# adaptor.net
KiCad netlist of a schematic drawn in EAGLE
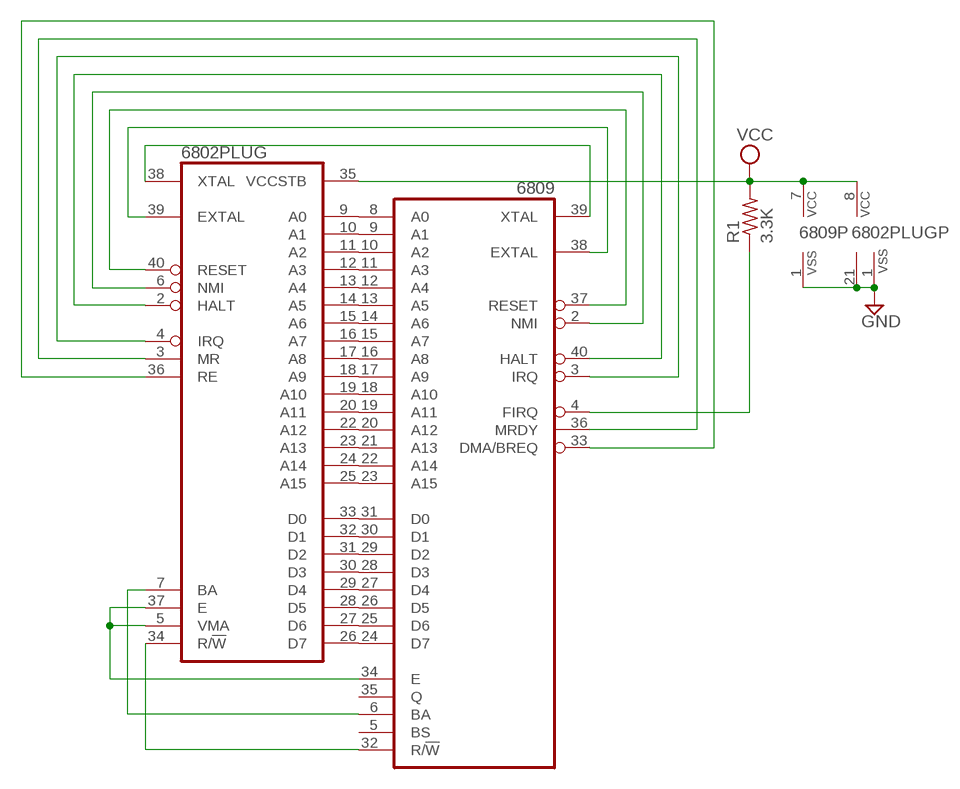
[diagram p0: schematic, sheet 1]

(export (version "E")
  (design (tool "Eeschema 10.0.6"))
  (components
    (comp (ref "6802PLUG")
      (value "6802")
      (footprint "eagle-import:DIL40")
      (libsource (lib "eagle-import") (part "6802"))
    )
    (comp (ref "6809")
      (value "6809")
      (footprint "eagle-import:DIL40")
      (fields (field (name "MF") "NTE ELECTRONICS") (field (name "MPN") "NTE6809"))
      (libsource (lib "eagle-import") (part "6809"))
    )
    (comp (ref "R1")
      (value "3.3K")
      (footprint "eagle-import:0207_10")
      (libsource (lib "eagle-import") (part "R-US_0207/10"))
    )
  )
  (nets
    (net (code "1") (name "GND") (class "Default")
      (node (ref "6802PLUG") (pin "1") (pinfunction "VSS_1") (pintype "power_in"))
      (node (ref "6802PLUG") (pin "21") (pinfunction "VSS_21") (pintype "power_in"))
      (node (ref "6809") (pin "1") (pinfunction "VSS_1") (pintype "power_in"))
    )
    (net (code "2") (name "Net-(6802PLUGA-A0)") (class "Default")
      (node (ref "6802PLUG") (pin "9") (pinfunction "A0_9") (pintype "output"))
      (node (ref "6809") (pin "8") (pinfunction "A0_8") (pintype "tri_state"))
    )
    (net (code "3") (name "Net-(6802PLUGA-A1)") (class "Default")
      (node (ref "6802PLUG") (pin "10") (pinfunction "A1_10") (pintype "output"))
      (node (ref "6809") (pin "9") (pinfunction "A1_9") (pintype "tri_state"))
    )
    (net (code "4") (name "Net-(6802PLUGA-A2)") (class "Default")
      (node (ref "6802PLUG") (pin "11") (pinfunction "A2_11") (pintype "output"))
      (node (ref "6809") (pin "10") (pinfunction "A2_10") (pintype "tri_state"))
    )
    (net (code "5") (name "Net-(6802PLUGA-A3)") (class "Default")
      (node (ref "6802PLUG") (pin "12") (pinfunction "A3_12") (pintype "output"))
      (node (ref "6809") (pin "11") (pinfunction "A3_11") (pintype "tri_state"))
    )
    (net (code "6") (name "Net-(6802PLUGA-A4)") (class "Default")
      (node (ref "6802PLUG") (pin "13") (pinfunction "A4_13") (pintype "output"))
      (node (ref "6809") (pin "12") (pinfunction "A4_12") (pintype "tri_state"))
    )
    (net (code "7") (name "Net-(6802PLUGA-A5)") (class "Default")
      (node (ref "6802PLUG") (pin "14") (pinfunction "A5_14") (pintype "output"))
      (node (ref "6809") (pin "13") (pinfunction "A5_13") (pintype "tri_state"))
    )
    (net (code "8") (name "Net-(6802PLUGA-A6)") (class "Default")
      (node (ref "6802PLUG") (pin "15") (pinfunction "A6_15") (pintype "output"))
      (node (ref "6809") (pin "14") (pinfunction "A6_14") (pintype "tri_state"))
    )
    (net (code "9") (name "Net-(6802PLUGA-A7)") (class "Default")
      (node (ref "6802PLUG") (pin "16") (pinfunction "A7_16") (pintype "output"))
      (node (ref "6809") (pin "15") (pinfunction "A7_15") (pintype "tri_state"))
    )
    (net (code "10") (name "Net-(6802PLUGA-A8)") (class "Default")
      (node (ref "6802PLUG") (pin "17") (pinfunction "A8_17") (pintype "output"))
      (node (ref "6809") (pin "16") (pinfunction "A8_16") (pintype "tri_state"))
    )
    (net (code "11") (name "Net-(6802PLUGA-A9)") (class "Default")
      (node (ref "6802PLUG") (pin "18") (pinfunction "A9_18") (pintype "output"))
      (node (ref "6809") (pin "17") (pinfunction "A9_17") (pintype "tri_state"))
    )
    (net (code "12") (name "Net-(6802PLUGA-A10)") (class "Default")
      (node (ref "6802PLUG") (pin "19") (pinfunction "A10_19") (pintype "output"))
      (node (ref "6809") (pin "18") (pinfunction "A10_18") (pintype "tri_state"))
    )
    (net (code "13") (name "Net-(6802PLUGA-A11)") (class "Default")
      (node (ref "6802PLUG") (pin "20") (pinfunction "A11_20") (pintype "output"))
      (node (ref "6809") (pin "19") (pinfunction "A11_19") (pintype "tri_state"))
    )
    (net (code "14") (name "Net-(6802PLUGA-A12)") (class "Default")
      (node (ref "6802PLUG") (pin "22") (pinfunction "A12_22") (pintype "output"))
      (node (ref "6809") (pin "20") (pinfunction "A12_20") (pintype "tri_state"))
    )
    (net (code "15") (name "Net-(6802PLUGA-A13)") (class "Default")
      (node (ref "6802PLUG") (pin "23") (pinfunction "A13_23") (pintype "output"))
      (node (ref "6809") (pin "21") (pinfunction "A13_21") (pintype "tri_state"))
    )
    (net (code "16") (name "Net-(6802PLUGA-A14)") (class "Default")
      (node (ref "6802PLUG") (pin "24") (pinfunction "A14_24") (pintype "output"))
      (node (ref "6809") (pin "22") (pinfunction "A14_22") (pintype "tri_state"))
    )
    (net (code "17") (name "Net-(6802PLUGA-A15)") (class "Default")
      (node (ref "6802PLUG") (pin "25") (pinfunction "A15_25") (pintype "output"))
      (node (ref "6809") (pin "23") (pinfunction "A15_23") (pintype "tri_state"))
    )
    (net (code "18") (name "Net-(6802PLUGA-BA)") (class "Default")
      (node (ref "6802PLUG") (pin "7") (pinfunction "BA_7") (pintype "output"))
      (node (ref "6809") (pin "6") (pinfunction "BA_6") (pintype "output"))
    )
    (net (code "19") (name "Net-(6802PLUGA-D0)") (class "Default")
      (node (ref "6802PLUG") (pin "33") (pinfunction "D0_33") (pintype "bidirectional"))
      (node (ref "6809") (pin "31") (pinfunction "D0_31") (pintype "bidirectional"))
    )
    (net (code "20") (name "Net-(6802PLUGA-D1)") (class "Default")
      (node (ref "6802PLUG") (pin "32") (pinfunction "D1_32") (pintype "bidirectional"))
      (node (ref "6809") (pin "30") (pinfunction "D1_30") (pintype "bidirectional"))
    )
    (net (code "21") (name "Net-(6802PLUGA-D2)") (class "Default")
      (node (ref "6802PLUG") (pin "31") (pinfunction "D2_31") (pintype "bidirectional"))
      (node (ref "6809") (pin "29") (pinfunction "D2_29") (pintype "bidirectional"))
    )
    (net (code "22") (name "Net-(6802PLUGA-D3)") (class "Default")
      (node (ref "6802PLUG") (pin "30") (pinfunction "D3_30") (pintype "bidirectional"))
      (node (ref "6809") (pin "28") (pinfunction "D3_28") (pintype "bidirectional"))
    )
    (net (code "23") (name "Net-(6802PLUGA-D4)") (class "Default")
      (node (ref "6802PLUG") (pin "29") (pinfunction "D4_29") (pintype "bidirectional"))
      (node (ref "6809") (pin "27") (pinfunction "D4_27") (pintype "bidirectional"))
    )
    (net (code "24") (name "Net-(6802PLUGA-D5)") (class "Default")
      (node (ref "6802PLUG") (pin "28") (pinfunction "D5_28") (pintype "bidirectional"))
      (node (ref "6809") (pin "26") (pinfunction "D5_26") (pintype "bidirectional"))
    )
    (net (code "25") (name "Net-(6802PLUGA-D6)") (class "Default")
      (node (ref "6802PLUG") (pin "27") (pinfunction "D6_27") (pintype "bidirectional"))
      (node (ref "6809") (pin "25") (pinfunction "D6_25") (pintype "bidirectional"))
    )
    (net (code "26") (name "Net-(6802PLUGA-D7)") (class "Default")
      (node (ref "6802PLUG") (pin "26") (pinfunction "D7_26") (pintype "bidirectional"))
      (node (ref "6809") (pin "24") (pinfunction "D7_24") (pintype "bidirectional"))
    )
    (net (code "27") (name "Net-(6802PLUGA-E)") (class "Default")
      (node (ref "6802PLUG") (pin "37") (pinfunction "E_37") (pintype "output"))
      (node (ref "6802PLUG") (pin "5") (pinfunction "VMA_5") (pintype "output"))
      (node (ref "6809") (pin "34") (pinfunction "E_34") (pintype "output"))
    )
    (net (code "28") (name "Net-(6802PLUGA-EXTAL)") (class "Default")
      (node (ref "6802PLUG") (pin "39") (pinfunction "EXTAL_39") (pintype "input"))
      (node (ref "6809") (pin "38") (pinfunction "EXTAL_38") (pintype "input"))
    )
    (net (code "29") (name "Net-(6802PLUGA-HALT)") (class "Default")
      (node (ref "6802PLUG") (pin "2") (pinfunction "HALT_2") (pintype "input"))
      (node (ref "6809") (pin "40") (pinfunction "HALT_40") (pintype "input"))
    )
    (net (code "30") (name "Net-(6802PLUGA-IRQ)") (class "Default")
      (node (ref "6802PLUG") (pin "4") (pinfunction "IRQ_4") (pintype "input"))
      (node (ref "6809") (pin "3") (pinfunction "IRQ_3") (pintype "input"))
    )
    (net (code "31") (name "Net-(6802PLUGA-MR)") (class "Default")
      (node (ref "6802PLUG") (pin "3") (pinfunction "MR_3") (pintype "input"))
      (node (ref "6809") (pin "36") (pinfunction "MRDY_36") (pintype "input"))
    )
    (net (code "32") (name "Net-(6802PLUGA-NMI)") (class "Default")
      (node (ref "6802PLUG") (pin "6") (pinfunction "NMI_6") (pintype "input"))
      (node (ref "6809") (pin "2") (pinfunction "NMI_2") (pintype "input"))
    )
    (net (code "33") (name "Net-(6802PLUGA-RE)") (class "Default")
      (node (ref "6802PLUG") (pin "36") (pinfunction "RE_36") (pintype "input"))
      (node (ref "6809") (pin "33") (pinfunction "DMA/BREQ_33") (pintype "input"))
    )
    (net (code "34") (name "Net-(6802PLUGA-RESET)") (class "Default")
      (node (ref "6802PLUG") (pin "40") (pinfunction "RESET_40") (pintype "input"))
      (node (ref "6809") (pin "37") (pinfunction "RESET_37") (pintype "input"))
    )
    (net (code "35") (name "Net-(6802PLUGA-R{slash}~{W})") (class "Default")
      (node (ref "6802PLUG") (pin "34") (pinfunction "R/~{W}_34") (pintype "output"))
      (node (ref "6809") (pin "32") (pinfunction "R/~{W}_32") (pintype "output"))
    )
    (net (code "36") (name "Net-(6802PLUGA-XTAL)") (class "Default")
      (node (ref "6802PLUG") (pin "38") (pinfunction "XTAL_38") (pintype "input"))
      (node (ref "6809") (pin "39") (pinfunction "XTAL_39") (pintype "input"))
    )
    (net (code "37") (name "Net-(6809A-FIRQ)") (class "Default")
      (node (ref "6809") (pin "4") (pinfunction "FIRQ_4") (pintype "input"))
      (node (ref "R1") (pin "1") (pinfunction "1_1") (pintype "passive"))
    )
    (net (code "38") (name "VCC") (class "Default")
      (node (ref "6802PLUG") (pin "35") (pinfunction "VCCSTB_35") (pintype "input"))
      (node (ref "6802PLUG") (pin "8") (pinfunction "VCC_8") (pintype "power_in"))
      (node (ref "6809") (pin "7") (pinfunction "VCC_7") (pintype "power_in"))
      (node (ref "R1") (pin "2") (pinfunction "2_2") (pintype "passive"))
    )
    (net (code "39") (name "unconnected-(6809A-BS-Pad5)") (class "Default")
      (node (ref "6809") (pin "5") (pinfunction "BS_5") (pintype "output"))
    )
    (net (code "40") (name "unconnected-(6809A-Q-Pad35)") (class "Default")
      (node (ref "6809") (pin "35") (pinfunction "Q_35") (pintype "output"))
    )
  )
)
